# LED_GND_ZLayer_switch.net
KiCad netlist of a schematic drawn in Altium Designer
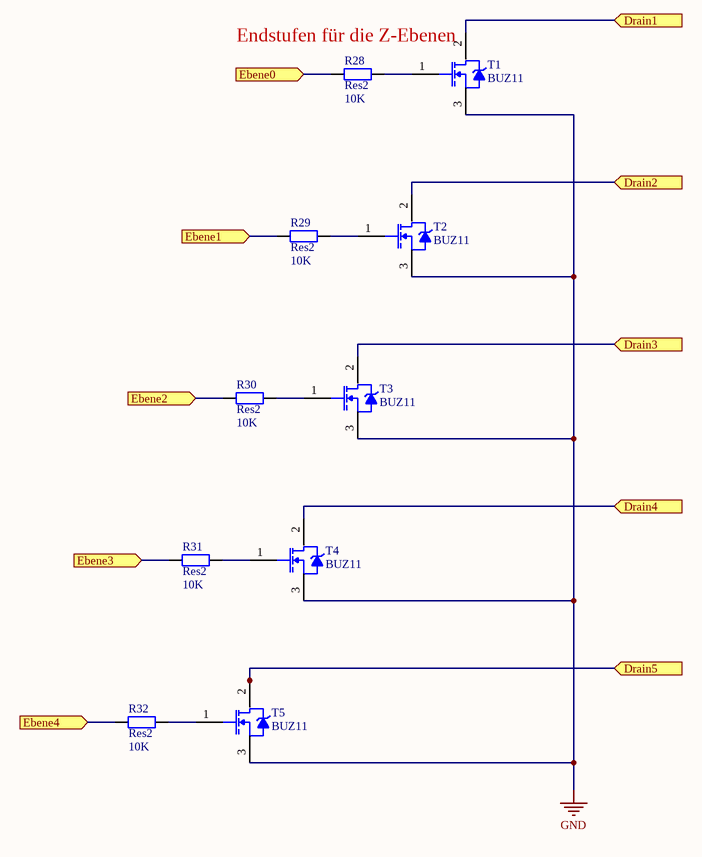
[diagram p0: LED_GND_ZLayer_switch.SchDoc]

(export (version "E")
  (design (tool "Eeschema 10.0.6"))
  (components
    (comp (ref "R28")
      (value "Res2")
      (footprint "AXIAL-0.4")
      (description "Resistor")
      (fields (field (name "ALTIUM_VALUE") "10K") (field (name "PUBLISHER") "Altium Limited"))
      (libsource (lib "Miscellaneous Devices") (part "Res2"))
    )
    (comp (ref "R29")
      (value "Res2")
      (footprint "AXIAL-0.4")
      (description "Resistor")
      (fields (field (name "ALTIUM_VALUE") "10K") (field (name "PUBLISHER") "Altium Limited"))
      (libsource (lib "Miscellaneous Devices") (part "Res2"))
    )
    (comp (ref "R30")
      (value "Res2")
      (footprint "AXIAL-0.4")
      (description "Resistor")
      (fields (field (name "ALTIUM_VALUE") "10K") (field (name "PUBLISHER") "Altium Limited"))
      (libsource (lib "Miscellaneous Devices") (part "Res2"))
    )
    (comp (ref "R31")
      (value "Res2")
      (footprint "AXIAL-0.4")
      (description "Resistor")
      (fields (field (name "ALTIUM_VALUE") "10K") (field (name "PUBLISHER") "Altium Limited"))
      (libsource (lib "Miscellaneous Devices") (part "Res2"))
    )
    (comp (ref "R32")
      (value "Res2")
      (footprint "AXIAL-0.4")
      (description "Resistor")
      (fields (field (name "ALTIUM_VALUE") "10K") (field (name "PUBLISHER") "Altium Limited"))
      (libsource (lib "Miscellaneous Devices") (part "Res2"))
    )
    (comp (ref "T1")
      (value "BUZ11")
      (footprint "Zetex Discrete MOSFET:TO220")
      (description "MOSFET")
      (libsource (lib "StdBT") (part "N-MOSFET"))
    )
    (comp (ref "T2")
      (value "BUZ11")
      (footprint "Zetex Discrete MOSFET:TO220")
      (description "MOSFET")
      (libsource (lib "StdBT") (part "N-MOSFET"))
    )
    (comp (ref "T3")
      (value "BUZ11")
      (footprint "Zetex Discrete MOSFET:TO220")
      (description "MOSFET")
      (libsource (lib "StdBT") (part "N-MOSFET"))
    )
    (comp (ref "T4")
      (value "BUZ11")
      (footprint "Zetex Discrete MOSFET:TO220")
      (description "MOSFET")
      (libsource (lib "StdBT") (part "N-MOSFET"))
    )
    (comp (ref "T5")
      (value "BUZ11")
      (footprint "Zetex Discrete MOSFET:TO220")
      (description "MOSFET")
      (libsource (lib "StdBT") (part "N-MOSFET"))
    )
  )
  (nets
    (net (code "1") (name "/Drain1") (class "Default")
      (node (ref "T1") (pin "2") (pinfunction "D_2") (pintype "passive"))
    )
    (net (code "2") (name "/Drain2") (class "Default")
      (node (ref "T2") (pin "2") (pinfunction "D_2") (pintype "passive"))
    )
    (net (code "3") (name "/Drain3") (class "Default")
      (node (ref "T3") (pin "2") (pinfunction "D_2") (pintype "passive"))
    )
    (net (code "4") (name "/Drain4") (class "Default")
      (node (ref "T4") (pin "2") (pinfunction "D_2") (pintype "passive"))
    )
    (net (code "5") (name "/Drain5") (class "Default")
      (node (ref "T5") (pin "2") (pinfunction "D_2") (pintype "passive"))
    )
    (net (code "6") (name "/Ebene0") (class "Default")
      (node (ref "R28") (pin "1") (pinfunction "1_1") (pintype "passive"))
    )
    (net (code "7") (name "/Ebene1") (class "Default")
      (node (ref "R29") (pin "1") (pinfunction "1_1") (pintype "passive"))
    )
    (net (code "8") (name "/Ebene2") (class "Default")
      (node (ref "R30") (pin "1") (pinfunction "1_1") (pintype "passive"))
    )
    (net (code "9") (name "/Ebene3") (class "Default")
      (node (ref "R31") (pin "1") (pinfunction "1_1") (pintype "passive"))
    )
    (net (code "10") (name "/Ebene4") (class "Default")
      (node (ref "R32") (pin "1") (pinfunction "1_1") (pintype "passive"))
    )
    (net (code "11") (name "GND") (class "Default")
      (node (ref "T1") (pin "3") (pinfunction "S_3") (pintype "passive"))
      (node (ref "T2") (pin "3") (pinfunction "S_3") (pintype "passive"))
      (node (ref "T3") (pin "3") (pinfunction "S_3") (pintype "passive"))
      (node (ref "T4") (pin "3") (pinfunction "S_3") (pintype "passive"))
      (node (ref "T5") (pin "3") (pinfunction "S_3") (pintype "passive"))
    )
    (net (code "12") (name "Net-(T1-G)") (class "Default")
      (node (ref "R28") (pin "2") (pinfunction "2_2") (pintype "passive"))
      (node (ref "T1") (pin "1") (pinfunction "G_1") (pintype "passive"))
    )
    (net (code "13") (name "Net-(T2-G)") (class "Default")
      (node (ref "R29") (pin "2") (pinfunction "2_2") (pintype "passive"))
      (node (ref "T2") (pin "1") (pinfunction "G_1") (pintype "passive"))
    )
    (net (code "14") (name "Net-(T3-G)") (class "Default")
      (node (ref "R30") (pin "2") (pinfunction "2_2") (pintype "passive"))
      (node (ref "T3") (pin "1") (pinfunction "G_1") (pintype "passive"))
    )
    (net (code "15") (name "Net-(T4-G)") (class "Default")
      (node (ref "R31") (pin "2") (pinfunction "2_2") (pintype "passive"))
      (node (ref "T4") (pin "1") (pinfunction "G_1") (pintype "passive"))
    )
    (net (code "16") (name "Net-(T5-G)") (class "Default")
      (node (ref "R32") (pin "2") (pinfunction "2_2") (pintype "passive"))
      (node (ref "T5") (pin "1") (pinfunction "G_1") (pintype "passive"))
    )
  )
)
